# 2_interface.net
KiCad netlist of a schematic drawn in Altium Designer
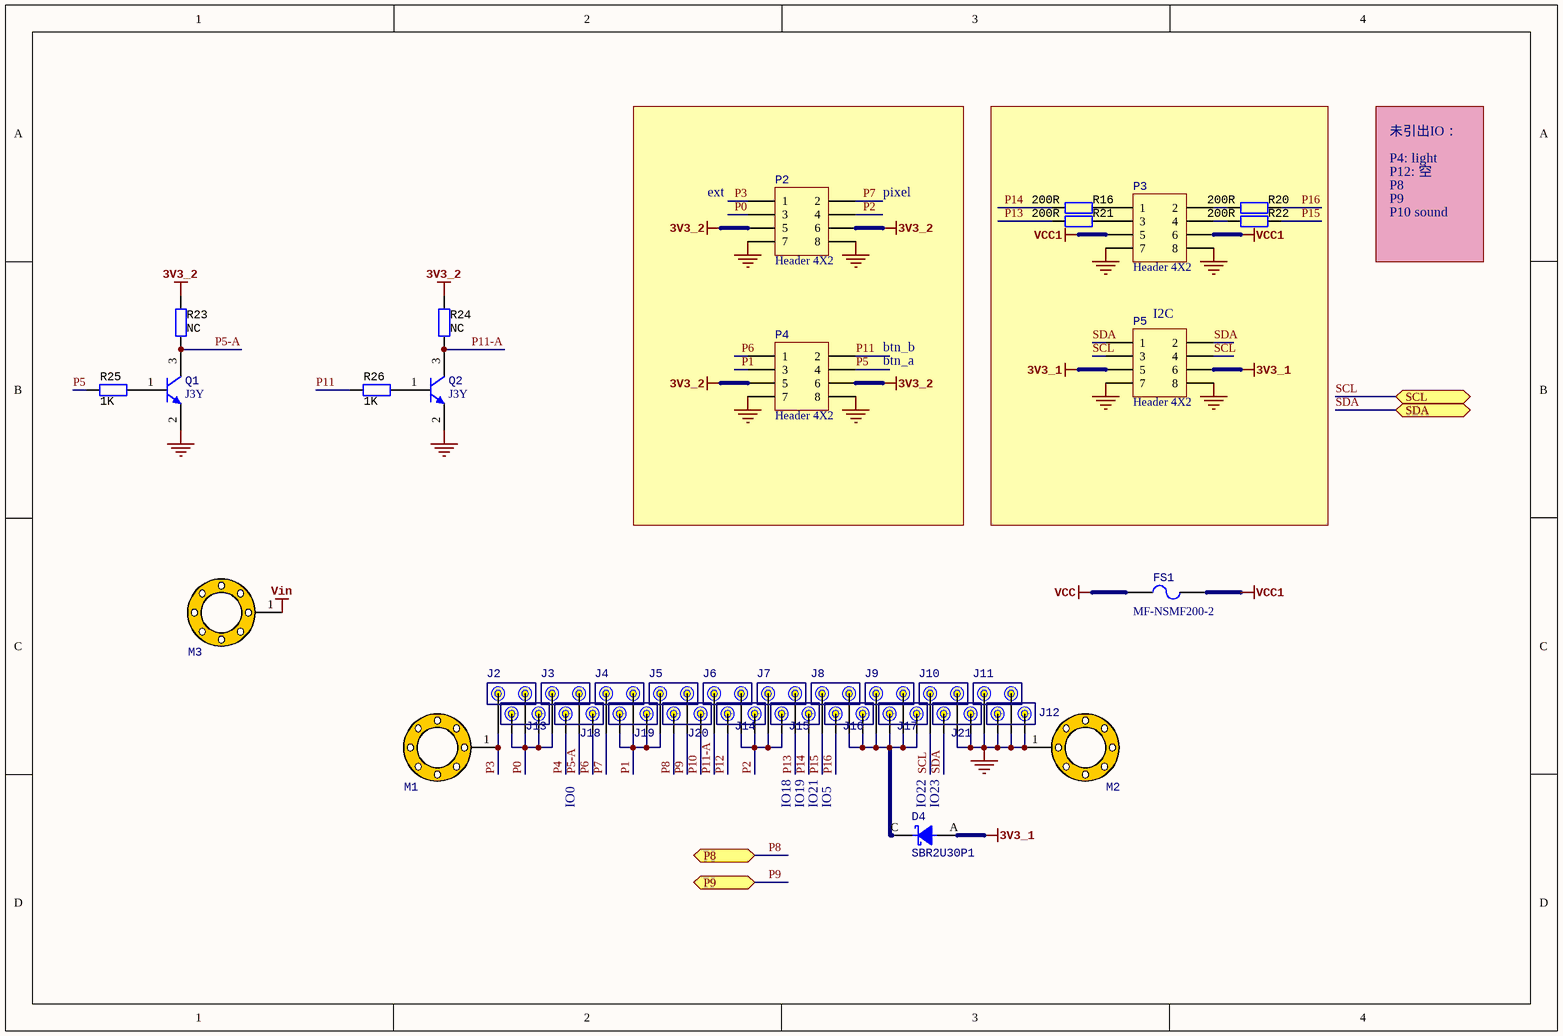
[diagram p0: 2.interface.SchDoc]

(export (version "E")
  (design (tool "Eeschema 10.0.6"))
  (components
    (comp (ref "D4")
      (value "SBR2U30P1")
      (footprint "POWERDI123")
      (fields (field (name "PARTNUMBER") "?") (field (name "PUBLISHER") "Altium Limited"))
      (libsource (lib "03.常用器件") (part "Diode_Schottky"))
    )
    (comp (ref "FS1")
      (value "MF-NSMF200-2")
      (footprint "R1206")
      (description "保险管")
      (libsource (lib "Miscellaneous Devices") (part "电子保险丝"))
    )
    (comp (ref "J2") (value "~") (footprint "顶针座子（2.54MM）") (libsource (lib "Schlib1") (part "pogopin")))
    (comp (ref "J3") (value "~") (footprint "顶针座子（2.54MM）") (libsource (lib "Schlib1") (part "pogopin")))
    (comp (ref "J4") (value "~") (footprint "顶针座子（2.54MM）") (libsource (lib "Schlib1") (part "pogopin")))
    (comp (ref "J5") (value "~") (footprint "顶针座子（2.54MM）") (libsource (lib "Schlib1") (part "pogopin")))
    (comp (ref "J6") (value "~") (footprint "顶针座子（2.54MM）") (libsource (lib "Schlib1") (part "pogopin")))
    (comp (ref "J7") (value "~") (footprint "顶针座子（2.54MM）") (libsource (lib "Schlib1") (part "pogopin")))
    (comp (ref "J8") (value "~") (footprint "顶针座子（2.54MM）") (libsource (lib "Schlib1") (part "pogopin")))
    (comp (ref "J9") (value "~") (footprint "顶针座子（2.54MM）") (libsource (lib "Schlib1") (part "pogopin")))
    (comp (ref "J10") (value "~") (footprint "顶针座子（2.54MM）") (libsource (lib "Schlib1") (part "pogopin")))
    (comp (ref "J11") (value "~") (footprint "顶针座子（2.54MM）") (libsource (lib "Schlib1") (part "pogopin")))
    (comp (ref "J12") (value "~") (footprint "顶针座子（2.54MM）") (libsource (lib "Schlib1") (part "pogopin_32")))
    (comp (ref "J13") (value "~") (footprint "顶针座子（2.54MM）") (libsource (lib "Schlib1") (part "pogopin_32")))
    (comp (ref "J14") (value "~") (footprint "顶针座子（2.54MM）") (libsource (lib "Schlib1") (part "pogopin_32")))
    (comp (ref "J15") (value "~") (footprint "顶针座子（2.54MM）") (libsource (lib "Schlib1") (part "pogopin_32")))
    (comp (ref "J16") (value "~") (footprint "顶针座子（2.54MM）") (libsource (lib "Schlib1") (part "pogopin_32")))
    (comp (ref "J17") (value "~") (footprint "顶针座子（2.54MM）") (libsource (lib "Schlib1") (part "pogopin_32")))
    (comp (ref "J18") (value "~") (footprint "顶针座子（2.54MM）") (libsource (lib "Schlib1") (part "pogopin_32")))
    (comp (ref "J19") (value "~") (footprint "顶针座子（2.54MM）") (libsource (lib "Schlib1") (part "pogopin_32")))
    (comp (ref "J20") (value "~") (footprint "顶针座子（2.54MM）") (libsource (lib "Schlib1") (part "pogopin_32")))
    (comp (ref "J21") (value "~") (footprint "顶针座子（2.54MM）") (libsource (lib "Schlib1") (part "pogopin_32")))
    (comp (ref "M1") (value "~") (footprint "3MM螺丝孔") (libsource (lib "labplus-connector") (part "screw")))
    (comp (ref "M2") (value "~") (footprint "3MM螺丝孔") (libsource (lib "labplus-connector") (part "screw")))
    (comp (ref "M3") (value "~") (footprint "3MM螺丝孔") (libsource (lib "labplus-connector") (part "screw")))
    (comp (ref "P2")
      (value "Header 4X2")
      (footprint "双拼弯角排针2.54/4P")
      (description "Header, 4-Pin, Dual row")
      (fields (field (name "PUBLISHER") "Altium Limited"))
      (libsource (lib "Miscellaneous Connectors") (part "Header 4X2"))
    )
    (comp (ref "P3")
      (value "Header 4X2")
      (footprint "双拼弯角排针2.54/4P")
      (description "Header, 4-Pin, Dual row")
      (fields (field (name "PUBLISHER") "Altium Limited"))
      (libsource (lib "Miscellaneous Connectors") (part "Header 4X2"))
    )
    (comp (ref "P4")
      (value "Header 4X2")
      (footprint "双拼弯角排针2.54/4P")
      (description "Header, 4-Pin, Dual row")
      (fields (field (name "PUBLISHER") "Altium Limited"))
      (libsource (lib "Miscellaneous Connectors") (part "Header 4X2"))
    )
    (comp (ref "P5")
      (value "Header 4X2")
      (footprint "双拼弯角排针2.54/4P")
      (description "Header, 4-Pin, Dual row")
      (fields (field (name "PUBLISHER") "Altium Limited"))
      (libsource (lib "Miscellaneous Connectors") (part "Header 4X2"))
    )
    (comp (ref "Q1")
      (value "J3Y")
      (footprint "DFN 3L")
      (description "NPN General Purpose Amplifier")
      (fields (field (name "PUBLISHER") "Altium Limited"))
      (libsource (lib "Schlib1") (part "2N3904"))
    )
    (comp (ref "Q2")
      (value "J3Y")
      (footprint "DFN 3L")
      (description "NPN General Purpose Amplifier")
      (fields (field (name "PUBLISHER") "Altium Limited"))
      (libsource (lib "Schlib1") (part "2N3904"))
    )
    (comp (ref "R16")
      (value "200R")
      (footprint "0402")
      (description "RES, 1.0k ohm, 5%, 0.1W, 0603")
      (fields
        (field (name "PARTNUMBER") "RC0603JR-071KL")
        (field (name "MANUFACTURER") "Yageo America")
        (field (name "PUBLISHER") "Texas Instruments")
      )
      (libsource (lib "03.常用器件") (part "RES1"))
    )
    (comp (ref "R20")
      (value "200R")
      (footprint "0402")
      (description "RES, 1.0k ohm, 5%, 0.1W, 0603")
      (fields
        (field (name "PARTNUMBER") "RC0603JR-071KL")
        (field (name "MANUFACTURER") "Yageo America")
        (field (name "PUBLISHER") "Texas Instruments")
      )
      (libsource (lib "03.常用器件") (part "RES1"))
    )
    (comp (ref "R21")
      (value "200R")
      (footprint "0402")
      (description "RES, 1.0k ohm, 5%, 0.1W, 0603")
      (fields
        (field (name "PARTNUMBER") "RC0603JR-071KL")
        (field (name "MANUFACTURER") "Yageo America")
        (field (name "PUBLISHER") "Texas Instruments")
      )
      (libsource (lib "03.常用器件") (part "RES1"))
    )
    (comp (ref "R22")
      (value "200R")
      (footprint "0402")
      (description "RES, 1.0k ohm, 5%, 0.1W, 0603")
      (fields
        (field (name "PARTNUMBER") "RC0603JR-071KL")
        (field (name "MANUFACTURER") "Yageo America")
        (field (name "PUBLISHER") "Texas Instruments")
      )
      (libsource (lib "03.常用器件") (part "RES1"))
    )
    (comp (ref "R23")
      (value "NC")
      (footprint "0402")
      (description "RES, 1.0k ohm, 5%, 0.1W, 0603")
      (fields
        (field (name "PARTNUMBER") "RC0603JR-071KL")
        (field (name "MANUFACTURER") "Yageo America")
        (field (name "PUBLISHER") "Texas Instruments")
      )
      (libsource (lib "") (part "RES1_1"))
    )
    (comp (ref "R24")
      (value "NC")
      (footprint "0402")
      (description "RES, 1.0k ohm, 5%, 0.1W, 0603")
      (fields
        (field (name "PARTNUMBER") "RC0603JR-071KL")
        (field (name "MANUFACTURER") "Yageo America")
        (field (name "PUBLISHER") "Texas Instruments")
      )
      (libsource (lib "") (part "RES1_1"))
    )
    (comp (ref "R25")
      (value "1K")
      (footprint "0402")
      (description "RES, 1.0k ohm, 5%, 0.1W, 0603")
      (fields
        (field (name "PARTNUMBER") "RC0603JR-071KL")
        (field (name "MANUFACTURER") "Yageo America")
        (field (name "PUBLISHER") "Texas Instruments")
      )
      (libsource (lib "") (part "RES1_2"))
    )
    (comp (ref "R26")
      (value "1K")
      (footprint "0402")
      (description "RES, 1.0k ohm, 5%, 0.1W, 0603")
      (fields
        (field (name "PARTNUMBER") "RC0603JR-071KL")
        (field (name "MANUFACTURER") "Yageo America")
        (field (name "PUBLISHER") "Texas Instruments")
      )
      (libsource (lib "") (part "RES1_2"))
    )
  )
  (nets
    (net (code "1") (name "/P0") (class "Default")
      (node (ref "J13") (pin "1") (pinfunction "1_1") (pintype "passive"))
      (node (ref "J13") (pin "2") (pinfunction "2_2") (pintype "passive"))
      (node (ref "J2") (pin "2") (pinfunction "2_2") (pintype "passive"))
      (node (ref "J3") (pin "1") (pinfunction "1_1") (pintype "passive"))
      (node (ref "P2") (pin "3") (pinfunction "3_3") (pintype "passive"))
    )
    (net (code "2") (name "/P1") (class "Default")
      (node (ref "J19") (pin "1") (pinfunction "1_1") (pintype "passive"))
      (node (ref "J19") (pin "2") (pinfunction "2_2") (pintype "passive"))
      (node (ref "J4") (pin "2") (pinfunction "2_2") (pintype "passive"))
      (node (ref "J5") (pin "1") (pinfunction "1_1") (pintype "passive"))
      (node (ref "P4") (pin "3") (pinfunction "3_3") (pintype "passive"))
    )
    (net (code "3") (name "/P2") (class "Default")
      (node (ref "J14") (pin "2") (pinfunction "2_2") (pintype "passive"))
      (node (ref "J15") (pin "1") (pinfunction "1_1") (pintype "passive"))
      (node (ref "J6") (pin "2") (pinfunction "2_2") (pintype "passive"))
      (node (ref "J7") (pin "1") (pinfunction "1_1") (pintype "passive"))
      (node (ref "P2") (pin "4") (pinfunction "4_4") (pintype "passive"))
    )
    (net (code "4") (name "/P3") (class "Default")
      (node (ref "J2") (pin "1") (pinfunction "1_1") (pintype "passive"))
      (node (ref "M1") (pin "1") (pinfunction "1_1") (pintype "passive"))
      (node (ref "P2") (pin "1") (pinfunction "1_1") (pintype "passive"))
    )
    (net (code "5") (name "/P4") (class "Default")
      (node (ref "J18") (pin "1") (pinfunction "1_1") (pintype "passive"))
    )
    (net (code "6") (name "/P5") (class "Default")
      (node (ref "P4") (pin "4") (pinfunction "4_4") (pintype "passive"))
      (node (ref "R25") (pin "1") (pinfunction "1_1") (pintype "passive"))
    )
    (net (code "7") (name "/P5-A") (class "Default")
      (node (ref "J3") (pin "2") (pinfunction "2_2") (pintype "passive"))
      (node (ref "Q1") (pin "3") (pinfunction "C_3") (pintype "passive"))
      (node (ref "R23") (pin "2") (pinfunction "2_2") (pintype "passive"))
    )
    (net (code "8") (name "/P6") (class "Default")
      (node (ref "J18") (pin "2") (pinfunction "2_2") (pintype "passive"))
      (node (ref "P4") (pin "1") (pinfunction "1_1") (pintype "passive"))
    )
    (net (code "9") (name "/P7") (class "Default")
      (node (ref "J4") (pin "1") (pinfunction "1_1") (pintype "passive"))
      (node (ref "P2") (pin "2") (pinfunction "2_2") (pintype "passive"))
    )
    (net (code "10") (name "/P8") (class "Default")
      (node (ref "J20") (pin "1") (pinfunction "1_1") (pintype "passive"))
    )
    (net (code "11") (name "/P9") (class "Default")
      (node (ref "J5") (pin "2") (pinfunction "2_2") (pintype "passive"))
    )
    (net (code "12") (name "/P10") (class "Default")
      (node (ref "J20") (pin "2") (pinfunction "2_2") (pintype "passive"))
    )
    (net (code "13") (name "/P11") (class "Default")
      (node (ref "P4") (pin "2") (pinfunction "2_2") (pintype "passive"))
      (node (ref "R26") (pin "1") (pinfunction "1_1") (pintype "passive"))
    )
    (net (code "14") (name "/P11-A") (class "Default")
      (node (ref "J6") (pin "1") (pinfunction "1_1") (pintype "passive"))
      (node (ref "Q2") (pin "3") (pinfunction "C_3") (pintype "passive"))
      (node (ref "R24") (pin "2") (pinfunction "2_2") (pintype "passive"))
    )
    (net (code "15") (name "/P12") (class "Default")
      (node (ref "J14") (pin "1") (pinfunction "1_1") (pintype "passive"))
    )
    (net (code "16") (name "/P13") (class "Default")
      (node (ref "J7") (pin "2") (pinfunction "2_2") (pintype "passive"))
      (node (ref "R21") (pin "1") (pinfunction "1_1") (pintype "passive"))
    )
    (net (code "17") (name "/P14") (class "Default")
      (node (ref "J15") (pin "2") (pinfunction "2_2") (pintype "passive"))
      (node (ref "R16") (pin "1") (pinfunction "1_1") (pintype "passive"))
    )
    (net (code "18") (name "/P15") (class "Default")
      (node (ref "J8") (pin "1") (pinfunction "1_1") (pintype "passive"))
      (node (ref "R22") (pin "2") (pinfunction "2_2") (pintype "passive"))
    )
    (net (code "19") (name "/P16") (class "Default")
      (node (ref "J16") (pin "1") (pinfunction "1_1") (pintype "passive"))
      (node (ref "R20") (pin "2") (pinfunction "2_2") (pintype "passive"))
    )
    (net (code "20") (name "/SCL") (class "Default")
      (node (ref "J10") (pin "1") (pinfunction "1_1") (pintype "passive"))
      (node (ref "P5") (pin "3") (pinfunction "3_3") (pintype "passive"))
      (node (ref "P5") (pin "4") (pinfunction "4_4") (pintype "passive"))
    )
    (net (code "21") (name "/SDA") (class "Default")
      (node (ref "J21") (pin "1") (pinfunction "1_1") (pintype "passive"))
      (node (ref "P5") (pin "1") (pinfunction "1_1") (pintype "passive"))
      (node (ref "P5") (pin "2") (pinfunction "2_2") (pintype "passive"))
    )
    (net (code "22") (name "3V3_1") (class "Default")
      (node (ref "D4") (pin "A") (pinfunction "ANODE_A") (pintype "passive"))
      (node (ref "P5") (pin "5") (pinfunction "5_5") (pintype "passive"))
      (node (ref "P5") (pin "6") (pinfunction "6_6") (pintype "passive"))
    )
    (net (code "23") (name "3V3_2") (class "Default")
      (node (ref "P2") (pin "5") (pinfunction "5_5") (pintype "passive"))
      (node (ref "P2") (pin "6") (pinfunction "6_6") (pintype "passive"))
      (node (ref "P4") (pin "5") (pinfunction "5_5") (pintype "passive"))
      (node (ref "P4") (pin "6") (pinfunction "6_6") (pintype "passive"))
      (node (ref "R23") (pin "1") (pinfunction "1_1") (pintype "passive"))
      (node (ref "R24") (pin "1") (pinfunction "1_1") (pintype "passive"))
    )
    (net (code "24") (name "<NO NET>") (class "Default")
      (node (ref "J10") (pin "2") (pinfunction "2_2") (pintype "passive"))
      (node (ref "J11") (pin "1") (pinfunction "1_1") (pintype "passive"))
      (node (ref "J11") (pin "2") (pinfunction "2_2") (pintype "passive"))
      (node (ref "J12") (pin "1") (pinfunction "1_1") (pintype "passive"))
      (node (ref "J12") (pin "2") (pinfunction "2_2") (pintype "passive"))
      (node (ref "J21") (pin "2") (pinfunction "2_2") (pintype "passive"))
      (node (ref "M2") (pin "1") (pinfunction "1_1") (pintype "passive"))
      (node (ref "P2") (pin "7") (pinfunction "7_7") (pintype "passive"))
      (node (ref "P2") (pin "8") (pinfunction "8_8") (pintype "passive"))
      (node (ref "P3") (pin "7") (pinfunction "7_7") (pintype "passive"))
      (node (ref "P3") (pin "8") (pinfunction "8_8") (pintype "passive"))
      (node (ref "P4") (pin "7") (pinfunction "7_7") (pintype "passive"))
      (node (ref "P4") (pin "8") (pinfunction "8_8") (pintype "passive"))
      (node (ref "P5") (pin "7") (pinfunction "7_7") (pintype "passive"))
      (node (ref "P5") (pin "8") (pinfunction "8_8") (pintype "passive"))
      (node (ref "Q1") (pin "2") (pinfunction "E_2") (pintype "passive"))
      (node (ref "Q2") (pin "2") (pinfunction "E_2") (pintype "passive"))
    )
    (net (code "25") (name "Net-(D4-CATHODE)") (class "Default")
      (node (ref "D4") (pin "C") (pinfunction "CATHODE_C") (pintype "passive"))
      (node (ref "J16") (pin "2") (pinfunction "2_2") (pintype "passive"))
      (node (ref "J17") (pin "1") (pinfunction "1_1") (pintype "passive"))
      (node (ref "J17") (pin "2") (pinfunction "2_2") (pintype "passive"))
      (node (ref "J8") (pin "2") (pinfunction "2_2") (pintype "passive"))
      (node (ref "J9") (pin "1") (pinfunction "1_1") (pintype "passive"))
      (node (ref "J9") (pin "2") (pinfunction "2_2") (pintype "passive"))
    )
    (net (code "26") (name "Net-(P3-Pad1)") (class "Default")
      (node (ref "P3") (pin "1") (pinfunction "1_1") (pintype "passive"))
      (node (ref "R16") (pin "2") (pinfunction "2_2") (pintype "passive"))
    )
    (net (code "27") (name "Net-(P3-Pad2)") (class "Default")
      (node (ref "P3") (pin "2") (pinfunction "2_2") (pintype "passive"))
      (node (ref "R20") (pin "1") (pinfunction "1_1") (pintype "passive"))
    )
    (net (code "28") (name "Net-(P3-Pad3)") (class "Default")
      (node (ref "P3") (pin "3") (pinfunction "3_3") (pintype "passive"))
      (node (ref "R21") (pin "2") (pinfunction "2_2") (pintype "passive"))
    )
    (net (code "29") (name "Net-(P3-Pad4)") (class "Default")
      (node (ref "P3") (pin "4") (pinfunction "4_4") (pintype "passive"))
      (node (ref "R22") (pin "1") (pinfunction "1_1") (pintype "passive"))
    )
    (net (code "30") (name "Net-(Q1-B)") (class "Default")
      (node (ref "Q1") (pin "1") (pinfunction "B_1") (pintype "passive"))
      (node (ref "R25") (pin "2") (pinfunction "2_2") (pintype "passive"))
    )
    (net (code "31") (name "Net-(Q2-B)") (class "Default")
      (node (ref "Q2") (pin "1") (pinfunction "B_1") (pintype "passive"))
      (node (ref "R26") (pin "2") (pinfunction "2_2") (pintype "passive"))
    )
    (net (code "32") (name "VCC") (class "Default")
      (node (ref "FS1") (pin "2") (pinfunction "1_2") (pintype "passive"))
    )
    (net (code "33") (name "VCC1") (class "Default")
      (node (ref "FS1") (pin "1") (pinfunction "0_1") (pintype "passive"))
      (node (ref "P3") (pin "5") (pinfunction "5_5") (pintype "passive"))
      (node (ref "P3") (pin "6") (pinfunction "6_6") (pintype "passive"))
    )
    (net (code "34") (name "Vin") (class "Default")
      (node (ref "M3") (pin "1") (pinfunction "1_1") (pintype "passive"))
    )
  )
)
